# AddMixShift.net
KiCad netlist of a schematic drawn in EAGLE
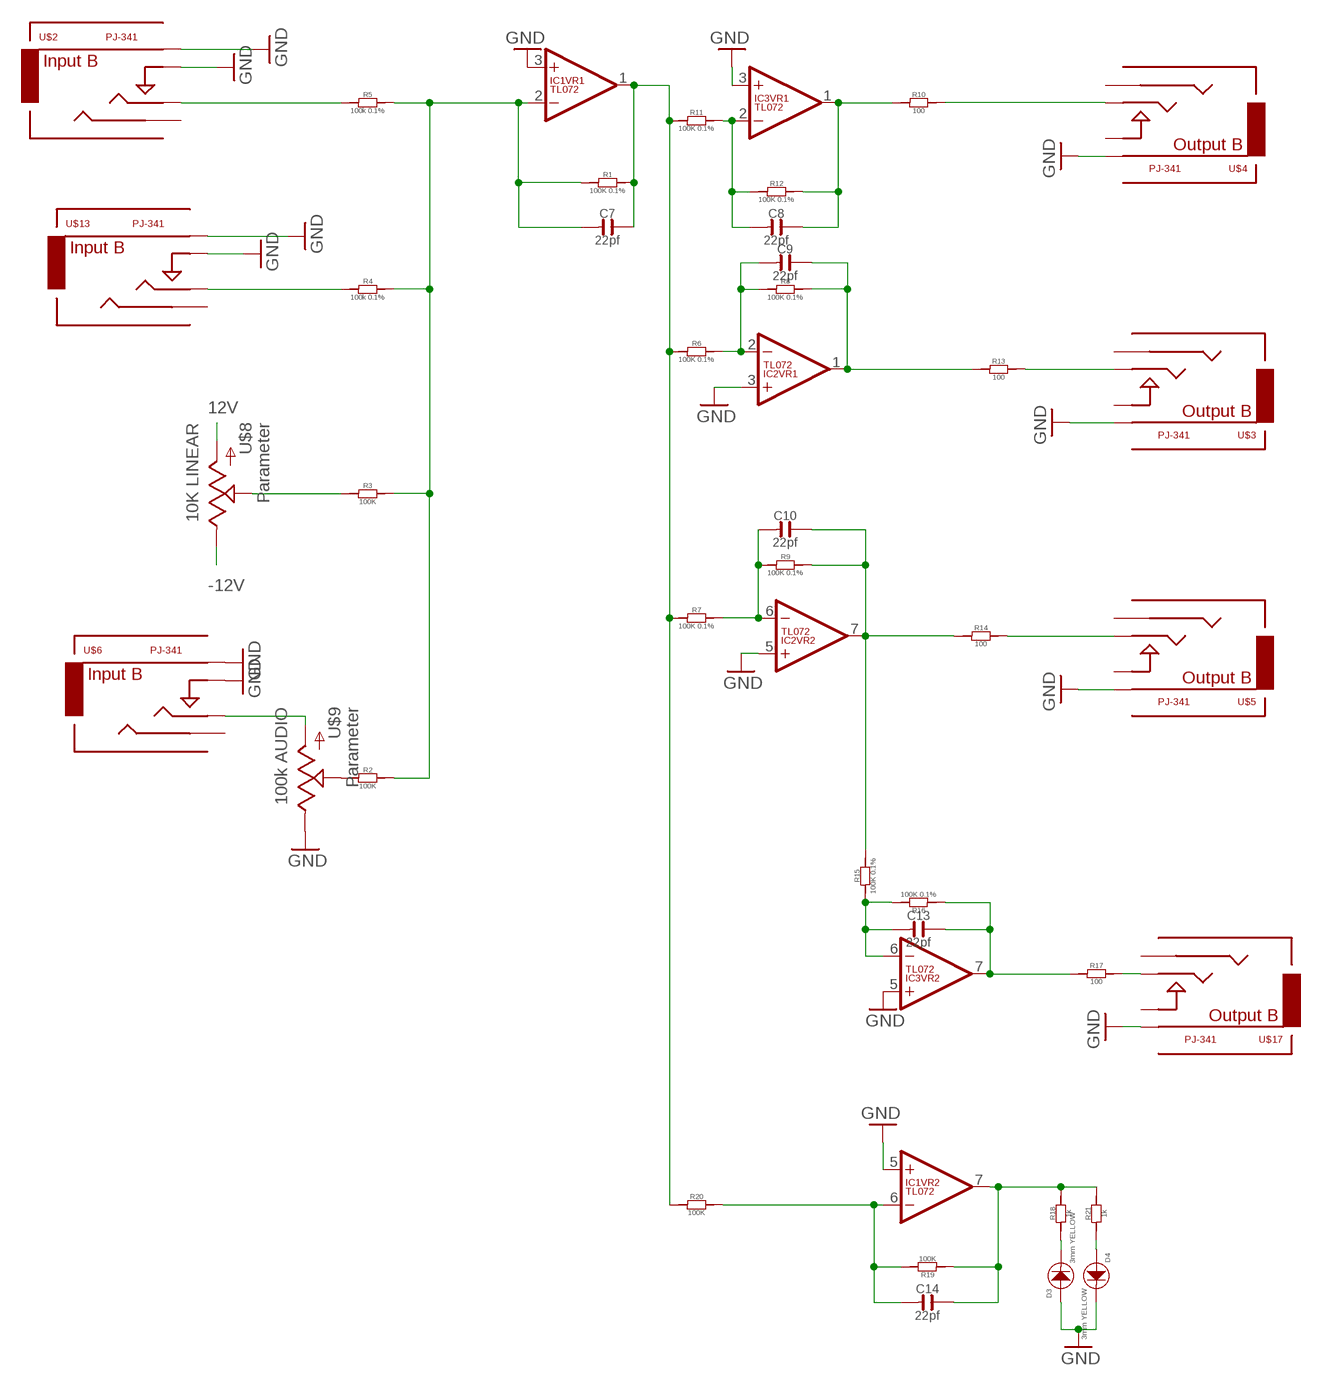
[diagram p0: schematic, sheet 1, part 1 of 2]
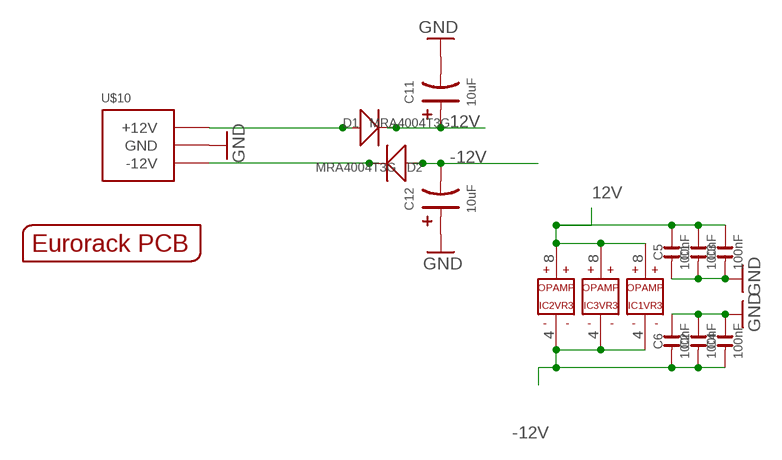
[diagram p1: schematic, sheet 1, part 2 of 2]

(export (version "E")
  (design (tool "Eeschema 10.0.6"))
  (components
    (comp (ref "C1")
      (value "100nF")
      (footprint "eagle-import:C0603")
      (libsource (lib "eagle-import") (part "C-0603"))
    )
    (comp (ref "C2")
      (value "100nF")
      (footprint "eagle-import:C0603")
      (libsource (lib "eagle-import") (part "C-0603"))
    )
    (comp (ref "C3")
      (value "100nF")
      (footprint "eagle-import:C0603")
      (libsource (lib "eagle-import") (part "C-0603"))
    )
    (comp (ref "C4")
      (value "100nF")
      (footprint "eagle-import:C0603")
      (libsource (lib "eagle-import") (part "C-0603"))
    )
    (comp (ref "C5")
      (value "100nF")
      (footprint "eagle-import:C0603")
      (libsource (lib "eagle-import") (part "C-0603"))
    )
    (comp (ref "C6")
      (value "100nF")
      (footprint "eagle-import:C0603")
      (libsource (lib "eagle-import") (part "C-0603"))
    )
    (comp (ref "C7")
      (value "22pf")
      (footprint "eagle-import:C0603")
      (libsource (lib "eagle-import") (part "C-0603"))
    )
    (comp (ref "C8")
      (value "22pf")
      (footprint "eagle-import:C0603")
      (libsource (lib "eagle-import") (part "C-0603"))
    )
    (comp (ref "C9")
      (value "22pf")
      (footprint "eagle-import:C0603")
      (libsource (lib "eagle-import") (part "C-0603"))
    )
    (comp (ref "C10")
      (value "22pf")
      (footprint "eagle-import:C0603")
      (libsource (lib "eagle-import") (part "C-0603"))
    )
    (comp (ref "C11")
      (value "10uF")
      (footprint "eagle-import:AVX-A")
      (libsource (lib "eagle-import") (part "C-POLAR-A"))
    )
    (comp (ref "C12")
      (value "10uF")
      (footprint "eagle-import:AVX-A")
      (libsource (lib "eagle-import") (part "C-POLAR-A"))
    )
    (comp (ref "C13")
      (value "22pf")
      (footprint "eagle-import:C0603")
      (libsource (lib "eagle-import") (part "C-0603"))
    )
    (comp (ref "C14")
      (value "22pf")
      (footprint "eagle-import:C0603")
      (libsource (lib "eagle-import") (part "C-0603"))
    )
    (comp (ref "D1")
      (value "MRA4004T3G")
      (footprint "eagle-import:DO-214AC")
      (fields (field (name "MF") "VISHAY") (field (name "MPN") "US1G-E3/5AT"))
      (libsource (lib "eagle-import") (part "D-SMA"))
    )
    (comp (ref "D2")
      (value "MRA4004T3G")
      (footprint "eagle-import:DO-214AC")
      (fields (field (name "MF") "VISHAY") (field (name "MPN") "US1G-E3/5AT"))
      (libsource (lib "eagle-import") (part "D-SMA"))
    )
    (comp (ref "D3")
      (value "3mm YELLOW")
      (footprint "eagle-import:3MMLED")
      (libsource (lib "eagle-import") (part "LED3MM"))
    )
    (comp (ref "D4")
      (value "3mm YELLOW")
      (footprint "eagle-import:3MMLED")
      (libsource (lib "eagle-import") (part "LED3MM"))
    )
    (comp (ref "IC1")
      (value "TL072")
      (footprint "eagle-import:SO08")
      (libsource (lib "eagle-import") (part "TL072"))
    )
    (comp (ref "IC2")
      (value "TL072")
      (footprint "eagle-import:SO08")
      (libsource (lib "eagle-import") (part "TL072"))
    )
    (comp (ref "IC3")
      (value "TL072")
      (footprint "eagle-import:SO08")
      (libsource (lib "eagle-import") (part "TL072"))
    )
    (comp (ref "R1")
      (value "100K 0.1%")
      (footprint "eagle-import:R0603")
      (libsource (lib "eagle-import") (part "R-0603"))
    )
    (comp (ref "R2")
      (value "100K")
      (footprint "eagle-import:R0603")
      (libsource (lib "eagle-import") (part "R-0603"))
    )
    (comp (ref "R3")
      (value "100K")
      (footprint "eagle-import:R0603")
      (libsource (lib "eagle-import") (part "R-0603"))
    )
    (comp (ref "R4")
      (value "100k 0.1%")
      (footprint "eagle-import:R0603")
      (libsource (lib "eagle-import") (part "R-0603"))
    )
    (comp (ref "R5")
      (value "100k 0.1%")
      (footprint "eagle-import:R0603")
      (libsource (lib "eagle-import") (part "R-0603"))
    )
    (comp (ref "R6")
      (value "100K 0.1%")
      (footprint "eagle-import:R0603")
      (libsource (lib "eagle-import") (part "R-0603"))
    )
    (comp (ref "R7")
      (value "100K 0.1%")
      (footprint "eagle-import:R0603")
      (libsource (lib "eagle-import") (part "R-0603"))
    )
    (comp (ref "R8")
      (value "100K 0.1%")
      (footprint "eagle-import:R0603")
      (libsource (lib "eagle-import") (part "R-0603"))
    )
    (comp (ref "R9")
      (value "100K 0.1%")
      (footprint "eagle-import:R0603")
      (libsource (lib "eagle-import") (part "R-0603"))
    )
    (comp (ref "R10")
      (value "100")
      (footprint "eagle-import:R0603")
      (libsource (lib "eagle-import") (part "R-0603"))
    )
    (comp (ref "R11")
      (value "100K 0.1%")
      (footprint "eagle-import:R0603")
      (libsource (lib "eagle-import") (part "R-0603"))
    )
    (comp (ref "R12")
      (value "100K 0.1%")
      (footprint "eagle-import:R0603")
      (libsource (lib "eagle-import") (part "R-0603"))
    )
    (comp (ref "R13")
      (value "100")
      (footprint "eagle-import:R0603")
      (libsource (lib "eagle-import") (part "R-0603"))
    )
    (comp (ref "R14")
      (value "100")
      (footprint "eagle-import:R0603")
      (libsource (lib "eagle-import") (part "R-0603"))
    )
    (comp (ref "R15")
      (value "100K 0.1%")
      (footprint "eagle-import:R0603")
      (libsource (lib "eagle-import") (part "R-0603"))
    )
    (comp (ref "R16")
      (value "100K 0.1%")
      (footprint "eagle-import:R0603")
      (libsource (lib "eagle-import") (part "R-0603"))
    )
    (comp (ref "R17")
      (value "100")
      (footprint "eagle-import:R0603")
      (libsource (lib "eagle-import") (part "R-0603"))
    )
    (comp (ref "R18")
      (value "1k")
      (footprint "eagle-import:R0603")
      (libsource (lib "eagle-import") (part "R-0603"))
    )
    (comp (ref "R19")
      (value "100K")
      (footprint "eagle-import:R0603")
      (libsource (lib "eagle-import") (part "R-0603"))
    )
    (comp (ref "R20")
      (value "100K")
      (footprint "eagle-import:R0603")
      (libsource (lib "eagle-import") (part "R-0603"))
    )
    (comp (ref "R21")
      (value "1k")
      (footprint "eagle-import:R0603")
      (libsource (lib "eagle-import") (part "R-0603"))
    )
    (comp (ref "U$1")
      (value "EURORACK_PCB4HP")
      (footprint "eagle-import:EURORACK4HPPCB")
      (libsource (lib "eagle-import") (part "EURORACK_PCB4HP"))
    )
    (comp (ref "U$2")
      (value "PJ-341")
      (footprint "eagle-import:3.5MM-JACK-SWITCH-13MM-INPUT")
      (fields (field (name "DESC") "Input B"))
      (libsource (lib "eagle-import") (part "AUDIO-JACKINPUT"))
    )
    (comp (ref "U$3")
      (value "PJ-341")
      (footprint "eagle-import:3.5MM-JACK-SWITCH-13MM-OUTPUT")
      (fields (field (name "DESC") "Output B"))
      (libsource (lib "eagle-import") (part "AUDIO-JACKOUTPUT"))
    )
    (comp (ref "U$4")
      (value "PJ-341")
      (footprint "eagle-import:3.5MM-JACK-SWITCH-13MM-OUTPUT")
      (fields (field (name "DESC") "Output B"))
      (libsource (lib "eagle-import") (part "AUDIO-JACKOUTPUT"))
    )
    (comp (ref "U$5")
      (value "PJ-341")
      (footprint "eagle-import:3.5MM-JACK-SWITCH-13MM-OUTPUT")
      (fields (field (name "DESC") "Output B"))
      (libsource (lib "eagle-import") (part "AUDIO-JACKOUTPUT"))
    )
    (comp (ref "U$6")
      (value "PJ-341")
      (footprint "eagle-import:3.5MM-JACK-SWITCH-13MM-INPUT")
      (fields (field (name "DESC") "Input B"))
      (libsource (lib "eagle-import") (part "AUDIO-JACKINPUT"))
    )
    (comp (ref "U$8")
      (value "10K LINEAR")
      (footprint "eagle-import:OG-POTS_ALPS_POT_VERTICAL")
      (libsource (lib "eagle-import") (part "POTZEPHPOT"))
    )
    (comp (ref "U$9")
      (value "100k AUDIO")
      (footprint "eagle-import:OG-POTS_ALPS_POT_VERTICAL")
      (libsource (lib "eagle-import") (part "POTZEPHPOT"))
    )
    (comp (ref "U$10")
      (value "POWER_SIMPLE")
      (footprint "eagle-import:2X05_SMT_HEADER")
      (libsource (lib "eagle-import") (part "POWER_SIMPLE"))
    )
    (comp (ref "U$13")
      (value "PJ-341")
      (footprint "eagle-import:3.5MM-JACK-SWITCH-13MM-INPUT")
      (fields (field (name "DESC") "Input B"))
      (libsource (lib "eagle-import") (part "AUDIO-JACKINPUT"))
    )
    (comp (ref "U$17")
      (value "PJ-341")
      (footprint "eagle-import:3.5MM-JACK-SWITCH-13MM-OUTPUT")
      (fields (field (name "DESC") "Output B"))
      (libsource (lib "eagle-import") (part "AUDIO-JACKOUTPUT"))
    )
  )
  (nets
    (net (code "1") (name "/-12V") (class "Default")
      (node (ref "C12") (pin "-") (pinfunction "2_-") (pintype "bidirectional"))
      (node (ref "C2") (pin "1") (pinfunction "1_1") (pintype "bidirectional"))
      (node (ref "C4") (pin "1") (pinfunction "1_1") (pintype "bidirectional"))
      (node (ref "C6") (pin "1") (pinfunction "1_1") (pintype "bidirectional"))
      (node (ref "D2") (pin "1") (pinfunction "+_1") (pintype "passive"))
      (node (ref "IC1") (pin "4") (pinfunction "V-_4") (pintype "power_in"))
      (node (ref "IC2") (pin "4") (pinfunction "V-_4") (pintype "power_in"))
      (node (ref "IC3") (pin "4") (pinfunction "V-_4") (pintype "power_in"))
      (node (ref "U$8") (pin "P$1") (pinfunction "E_P$1") (pintype "passive"))
    )
    (net (code "2") (name "/12V") (class "Default")
      (node (ref "C1") (pin "2") (pinfunction "2_2") (pintype "bidirectional"))
      (node (ref "C11") (pin "+") (pinfunction "1_+") (pintype "bidirectional"))
      (node (ref "C3") (pin "2") (pinfunction "2_2") (pintype "bidirectional"))
      (node (ref "C5") (pin "2") (pinfunction "2_2") (pintype "bidirectional"))
      (node (ref "D1") (pin "2") (pinfunction "-_2") (pintype "passive"))
      (node (ref "IC1") (pin "8") (pinfunction "V+_8") (pintype "power_in"))
      (node (ref "IC2") (pin "8") (pinfunction "V+_8") (pintype "power_in"))
      (node (ref "IC3") (pin "8") (pinfunction "V+_8") (pintype "power_in"))
      (node (ref "U$8") (pin "P$3") (pinfunction "A_P$3") (pintype "passive"))
    )
    (net (code "3") (name "GND") (class "Default")
      (node (ref "C1") (pin "1") (pinfunction "1_1") (pintype "bidirectional"))
      (node (ref "C11") (pin "-") (pinfunction "2_-") (pintype "bidirectional"))
      (node (ref "C12") (pin "+") (pinfunction "1_+") (pintype "bidirectional"))
      (node (ref "C2") (pin "2") (pinfunction "2_2") (pintype "bidirectional"))
      (node (ref "C3") (pin "1") (pinfunction "1_1") (pintype "bidirectional"))
      (node (ref "C4") (pin "2") (pinfunction "2_2") (pintype "bidirectional"))
      (node (ref "C5") (pin "1") (pinfunction "1_1") (pintype "bidirectional"))
      (node (ref "C6") (pin "2") (pinfunction "2_2") (pintype "bidirectional"))
      (node (ref "D3") (pin "+") (pinfunction "+_+") (pintype "passive"))
      (node (ref "D4") (pin "-") (pinfunction "-_-") (pintype "passive"))
      (node (ref "IC1") (pin "3") (pinfunction "+IN_3") (pintype "input"))
      (node (ref "IC1") (pin "5") (pinfunction "+IN_5") (pintype "input"))
      (node (ref "IC2") (pin "3") (pinfunction "+IN_3") (pintype "input"))
      (node (ref "IC2") (pin "5") (pinfunction "+IN_5") (pintype "input"))
      (node (ref "IC3") (pin "3") (pinfunction "+IN_3") (pintype "input"))
      (node (ref "IC3") (pin "5") (pinfunction "+IN_5") (pintype "input"))
      (node (ref "U$10") (pin "3") (pinfunction "GND_3") (pintype "bidirectional"))
      (node (ref "U$10") (pin "4") (pinfunction "GND_4") (pintype "bidirectional"))
      (node (ref "U$10") (pin "5") (pinfunction "GND_5") (pintype "bidirectional"))
      (node (ref "U$10") (pin "6") (pinfunction "GND_6") (pintype "bidirectional"))
      (node (ref "U$10") (pin "7") (pinfunction "GND_7") (pintype "bidirectional"))
      (node (ref "U$10") (pin "8") (pinfunction "GND_8") (pintype "bidirectional"))
      (node (ref "U$13") (pin "RING@3") (pinfunction "RING_RING@3") (pintype "bidirectional"))
      (node (ref "U$13") (pin "SWITCH@3") (pinfunction "SWITCH_SWITCH@3") (pintype "bidirectional"))
      (node (ref "U$17") (pin "RING@3") (pinfunction "RING_RING@3") (pintype "bidirectional"))
      (node (ref "U$2") (pin "RING@3") (pinfunction "RING_RING@3") (pintype "bidirectional"))
      (node (ref "U$2") (pin "SWITCH@3") (pinfunction "SWITCH_SWITCH@3") (pintype "bidirectional"))
      (node (ref "U$3") (pin "RING@3") (pinfunction "RING_RING@3") (pintype "bidirectional"))
      (node (ref "U$4") (pin "RING@3") (pinfunction "RING_RING@3") (pintype "bidirectional"))
      (node (ref "U$5") (pin "RING@3") (pinfunction "RING_RING@3") (pintype "bidirectional"))
      (node (ref "U$6") (pin "RING@3") (pinfunction "RING_RING@3") (pintype "bidirectional"))
      (node (ref "U$6") (pin "SWITCH@3") (pinfunction "SWITCH_SWITCH@3") (pintype "bidirectional"))
      (node (ref "U$9") (pin "P$1") (pinfunction "E_P$1") (pintype "passive"))
    )
    (net (code "4") (name "Net-(D1-+)") (class "Default")
      (node (ref "D1") (pin "1") (pinfunction "+_1") (pintype "passive"))
      (node (ref "U$10") (pin "10") (pinfunction "+12V_10") (pintype "bidirectional"))
      (node (ref "U$10") (pin "9") (pinfunction "+12V_9") (pintype "bidirectional"))
    )
    (net (code "5") (name "Net-(D2--)") (class "Default")
      (node (ref "D2") (pin "2") (pinfunction "-_2") (pintype "passive"))
      (node (ref "U$10") (pin "1") (pinfunction "-12V_1") (pintype "bidirectional"))
      (node (ref "U$10") (pin "2") (pinfunction "-12V_2") (pintype "bidirectional"))
    )
    (net (code "6") (name "Net-(D3-Pad-)") (class "Default")
      (node (ref "D3") (pin "-") (pinfunction "-_-") (pintype "passive"))
      (node (ref "R18") (pin "1") (pinfunction "1_1") (pintype "bidirectional"))
    )
    (net (code "7") (name "Net-(D4-Pad+)") (class "Default")
      (node (ref "D4") (pin "+") (pinfunction "+_+") (pintype "passive"))
      (node (ref "R21") (pin "1") (pinfunction "1_1") (pintype "bidirectional"))
    )
    (net (code "8") (name "Net-(IC1A--IN)") (class "Default")
      (node (ref "C7") (pin "1") (pinfunction "1_1") (pintype "bidirectional"))
      (node (ref "IC1") (pin "2") (pinfunction "-IN_2") (pintype "input"))
      (node (ref "R1") (pin "1") (pinfunction "1_1") (pintype "bidirectional"))
      (node (ref "R2") (pin "2") (pinfunction "2_2") (pintype "bidirectional"))
      (node (ref "R3") (pin "2") (pinfunction "2_2") (pintype "bidirectional"))
      (node (ref "R4") (pin "2") (pinfunction "2_2") (pintype "bidirectional"))
      (node (ref "R5") (pin "2") (pinfunction "2_2") (pintype "bidirectional"))
    )
    (net (code "9") (name "Net-(IC1A-OUT)") (class "Default")
      (node (ref "C7") (pin "2") (pinfunction "2_2") (pintype "bidirectional"))
      (node (ref "IC1") (pin "1") (pinfunction "OUT_1") (pintype "output"))
      (node (ref "R1") (pin "2") (pinfunction "2_2") (pintype "bidirectional"))
      (node (ref "R11") (pin "1") (pinfunction "1_1") (pintype "bidirectional"))
      (node (ref "R20") (pin "1") (pinfunction "1_1") (pintype "bidirectional"))
      (node (ref "R6") (pin "1") (pinfunction "1_1") (pintype "bidirectional"))
      (node (ref "R7") (pin "1") (pinfunction "1_1") (pintype "bidirectional"))
    )
    (net (code "10") (name "Net-(IC1B--IN)") (class "Default")
      (node (ref "C14") (pin "1") (pinfunction "1_1") (pintype "bidirectional"))
      (node (ref "IC1") (pin "6") (pinfunction "-IN_6") (pintype "input"))
      (node (ref "R19") (pin "2") (pinfunction "2_2") (pintype "bidirectional"))
      (node (ref "R20") (pin "2") (pinfunction "2_2") (pintype "bidirectional"))
    )
    (net (code "11") (name "Net-(IC1B-OUT)") (class "Default")
      (node (ref "C14") (pin "2") (pinfunction "2_2") (pintype "bidirectional"))
      (node (ref "IC1") (pin "7") (pinfunction "OUT_7") (pintype "output"))
      (node (ref "R18") (pin "2") (pinfunction "2_2") (pintype "bidirectional"))
      (node (ref "R19") (pin "1") (pinfunction "1_1") (pintype "bidirectional"))
      (node (ref "R21") (pin "2") (pinfunction "2_2") (pintype "bidirectional"))
    )
    (net (code "12") (name "Net-(IC2A--IN)") (class "Default")
      (node (ref "C9") (pin "1") (pinfunction "1_1") (pintype "bidirectional"))
      (node (ref "IC2") (pin "2") (pinfunction "-IN_2") (pintype "input"))
      (node (ref "R6") (pin "2") (pinfunction "2_2") (pintype "bidirectional"))
      (node (ref "R8") (pin "1") (pinfunction "1_1") (pintype "bidirectional"))
    )
    (net (code "13") (name "Net-(IC2A-OUT)") (class "Default")
      (node (ref "C9") (pin "2") (pinfunction "2_2") (pintype "bidirectional"))
      (node (ref "IC2") (pin "1") (pinfunction "OUT_1") (pintype "output"))
      (node (ref "R13") (pin "1") (pinfunction "1_1") (pintype "bidirectional"))
      (node (ref "R8") (pin "2") (pinfunction "2_2") (pintype "bidirectional"))
    )
    (net (code "14") (name "Net-(IC2B--IN)") (class "Default")
      (node (ref "C10") (pin "1") (pinfunction "1_1") (pintype "bidirectional"))
      (node (ref "IC2") (pin "6") (pinfunction "-IN_6") (pintype "input"))
      (node (ref "R7") (pin "2") (pinfunction "2_2") (pintype "bidirectional"))
      (node (ref "R9") (pin "1") (pinfunction "1_1") (pintype "bidirectional"))
    )
    (net (code "15") (name "Net-(IC2B-OUT)") (class "Default")
      (node (ref "C10") (pin "2") (pinfunction "2_2") (pintype "bidirectional"))
      (node (ref "IC2") (pin "7") (pinfunction "OUT_7") (pintype "output"))
      (node (ref "R14") (pin "1") (pinfunction "1_1") (pintype "bidirectional"))
      (node (ref "R15") (pin "2") (pinfunction "2_2") (pintype "bidirectional"))
      (node (ref "R9") (pin "2") (pinfunction "2_2") (pintype "bidirectional"))
    )
    (net (code "16") (name "Net-(IC3A--IN)") (class "Default")
      (node (ref "C8") (pin "1") (pinfunction "1_1") (pintype "bidirectional"))
      (node (ref "IC3") (pin "2") (pinfunction "-IN_2") (pintype "input"))
      (node (ref "R11") (pin "2") (pinfunction "2_2") (pintype "bidirectional"))
      (node (ref "R12") (pin "1") (pinfunction "1_1") (pintype "bidirectional"))
    )
    (net (code "17") (name "Net-(IC3A-OUT)") (class "Default")
      (node (ref "C8") (pin "2") (pinfunction "2_2") (pintype "bidirectional"))
      (node (ref "IC3") (pin "1") (pinfunction "OUT_1") (pintype "output"))
      (node (ref "R10") (pin "1") (pinfunction "1_1") (pintype "bidirectional"))
      (node (ref "R12") (pin "2") (pinfunction "2_2") (pintype "bidirectional"))
    )
    (net (code "18") (name "Net-(IC3B--IN)") (class "Default")
      (node (ref "C13") (pin "1") (pinfunction "1_1") (pintype "bidirectional"))
      (node (ref "IC3") (pin "6") (pinfunction "-IN_6") (pintype "input"))
      (node (ref "R15") (pin "1") (pinfunction "1_1") (pintype "bidirectional"))
      (node (ref "R16") (pin "2") (pinfunction "2_2") (pintype "bidirectional"))
    )
    (net (code "19") (name "Net-(IC3B-OUT)") (class "Default")
      (node (ref "C13") (pin "2") (pinfunction "2_2") (pintype "bidirectional"))
      (node (ref "IC3") (pin "7") (pinfunction "OUT_7") (pintype "output"))
      (node (ref "R16") (pin "1") (pinfunction "1_1") (pintype "bidirectional"))
      (node (ref "R17") (pin "1") (pinfunction "1_1") (pintype "bidirectional"))
    )
    (net (code "20") (name "Net-(U$2-TIP)") (class "Default")
      (node (ref "R5") (pin "1") (pinfunction "1_1") (pintype "bidirectional"))
      (node (ref "U$2") (pin "TIP@3") (pinfunction "TIP_TIP@3") (pintype "bidirectional"))
    )
    (net (code "21") (name "Net-(U$3-TIP)") (class "Default")
      (node (ref "R13") (pin "2") (pinfunction "2_2") (pintype "bidirectional"))
      (node (ref "U$3") (pin "TIP@3") (pinfunction "TIP_TIP@3") (pintype "bidirectional"))
    )
    (net (code "22") (name "Net-(U$4-TIP)") (class "Default")
      (node (ref "R10") (pin "2") (pinfunction "2_2") (pintype "bidirectional"))
      (node (ref "U$4") (pin "TIP@3") (pinfunction "TIP_TIP@3") (pintype "bidirectional"))
    )
    (net (code "23") (name "Net-(U$5-TIP)") (class "Default")
      (node (ref "R14") (pin "2") (pinfunction "2_2") (pintype "bidirectional"))
      (node (ref "U$5") (pin "TIP@3") (pinfunction "TIP_TIP@3") (pintype "bidirectional"))
    )
    (net (code "24") (name "Net-(U$6-TIP)") (class "Default")
      (node (ref "U$6") (pin "TIP@3") (pinfunction "TIP_TIP@3") (pintype "bidirectional"))
      (node (ref "U$9") (pin "P$3") (pinfunction "A_P$3") (pintype "passive"))
    )
    (net (code "25") (name "Net-(U$8-S)") (class "Default")
      (node (ref "R3") (pin "1") (pinfunction "1_1") (pintype "bidirectional"))
      (node (ref "U$8") (pin "P$2") (pinfunction "S_P$2") (pintype "passive"))
    )
    (net (code "26") (name "Net-(U$9-S)") (class "Default")
      (node (ref "R2") (pin "1") (pinfunction "1_1") (pintype "bidirectional"))
      (node (ref "U$9") (pin "P$2") (pinfunction "S_P$2") (pintype "passive"))
    )
    (net (code "27") (name "Net-(U$13-TIP)") (class "Default")
      (node (ref "R4") (pin "1") (pinfunction "1_1") (pintype "bidirectional"))
      (node (ref "U$13") (pin "TIP@3") (pinfunction "TIP_TIP@3") (pintype "bidirectional"))
    )
    (net (code "28") (name "Net-(U$17-TIP)") (class "Default")
      (node (ref "R17") (pin "2") (pinfunction "2_2") (pintype "bidirectional"))
      (node (ref "U$17") (pin "TIP@3") (pinfunction "TIP_TIP@3") (pintype "bidirectional"))
    )
    (net (code "29") (name "unconnected-(U$2-SECOND-PadSECOND@3)") (class "Default")
      (node (ref "U$2") (pin "SECOND@3") (pinfunction "SECOND_SECOND@3") (pintype "bidirectional"))
    )
    (net (code "30") (name "unconnected-(U$3-SECOND-PadSECOND@3)") (class "Default")
      (node (ref "U$3") (pin "SECOND@3") (pinfunction "SECOND_SECOND@3") (pintype "bidirectional"))
    )
    (net (code "31") (name "unconnected-(U$3-SWITCH-PadSWITCH@3)") (class "Default")
      (node (ref "U$3") (pin "SWITCH@3") (pinfunction "SWITCH_SWITCH@3") (pintype "bidirectional"))
    )
    (net (code "32") (name "unconnected-(U$4-SECOND-PadSECOND@3)") (class "Default")
      (node (ref "U$4") (pin "SECOND@3") (pinfunction "SECOND_SECOND@3") (pintype "bidirectional"))
    )
    (net (code "33") (name "unconnected-(U$4-SWITCH-PadSWITCH@3)") (class "Default")
      (node (ref "U$4") (pin "SWITCH@3") (pinfunction "SWITCH_SWITCH@3") (pintype "bidirectional"))
    )
    (net (code "34") (name "unconnected-(U$5-SECOND-PadSECOND@3)") (class "Default")
      (node (ref "U$5") (pin "SECOND@3") (pinfunction "SECOND_SECOND@3") (pintype "bidirectional"))
    )
    (net (code "35") (name "unconnected-(U$5-SWITCH-PadSWITCH@3)") (class "Default")
      (node (ref "U$5") (pin "SWITCH@3") (pinfunction "SWITCH_SWITCH@3") (pintype "bidirectional"))
    )
    (net (code "36") (name "unconnected-(U$6-SECOND-PadSECOND@3)") (class "Default")
      (node (ref "U$6") (pin "SECOND@3") (pinfunction "SECOND_SECOND@3") (pintype "bidirectional"))
    )
    (net (code "37") (name "unconnected-(U$13-SECOND-PadSECOND@3)") (class "Default")
      (node (ref "U$13") (pin "SECOND@3") (pinfunction "SECOND_SECOND@3") (pintype "bidirectional"))
    )
    (net (code "38") (name "unconnected-(U$17-SECOND-PadSECOND@3)") (class "Default")
      (node (ref "U$17") (pin "SECOND@3") (pinfunction "SECOND_SECOND@3") (pintype "bidirectional"))
    )
    (net (code "39") (name "unconnected-(U$17-SWITCH-PadSWITCH@3)") (class "Default")
      (node (ref "U$17") (pin "SWITCH@3") (pinfunction "SWITCH_SWITCH@3") (pintype "bidirectional"))
    )
  )
)
